# buffered-mult-pcb-a.net
KiCad netlist of a schematic drawn in EAGLE
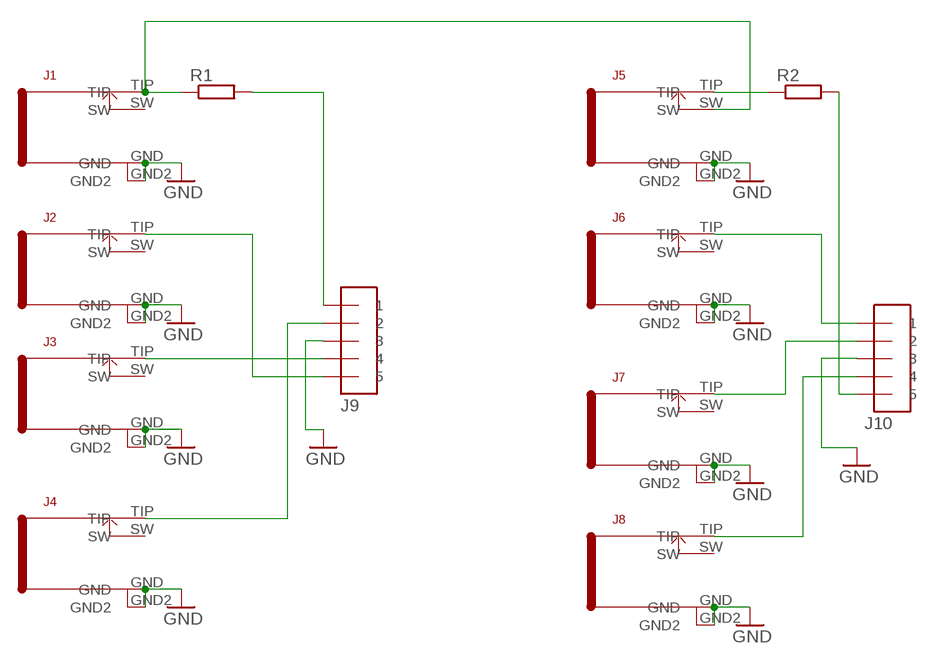
[diagram p0: schematic, sheet 1]

(export (version "E")
  (design (tool "Eeschema 10.0.6"))
  (components
    (comp (ref "J1")
      (value "WQP_PJ_301BM")
      (footprint "eagle-import:WQP_PJ_301BM")
      (libsource (lib "eagle-import") (part "WQP_PJ_301BM"))
    )
    (comp (ref "J2")
      (value "WQP_PJ_301BM")
      (footprint "eagle-import:WQP_PJ_301BM")
      (libsource (lib "eagle-import") (part "WQP_PJ_301BM"))
    )
    (comp (ref "J3")
      (value "WQP_PJ_301BM")
      (footprint "eagle-import:WQP_PJ_301BM")
      (libsource (lib "eagle-import") (part "WQP_PJ_301BM"))
    )
    (comp (ref "J4")
      (value "WQP_PJ_301BM")
      (footprint "eagle-import:WQP_PJ_301BM")
      (libsource (lib "eagle-import") (part "WQP_PJ_301BM"))
    )
    (comp (ref "J5")
      (value "WQP_PJ_301BM")
      (footprint "eagle-import:WQP_PJ_301BM")
      (libsource (lib "eagle-import") (part "WQP_PJ_301BM"))
    )
    (comp (ref "J6")
      (value "WQP_PJ_301BM")
      (footprint "eagle-import:WQP_PJ_301BM")
      (libsource (lib "eagle-import") (part "WQP_PJ_301BM"))
    )
    (comp (ref "J7")
      (value "WQP_PJ_301BM")
      (footprint "eagle-import:WQP_PJ_301BM")
      (libsource (lib "eagle-import") (part "WQP_PJ_301BM"))
    )
    (comp (ref "J8")
      (value "WQP_PJ_301BM")
      (footprint "eagle-import:WQP_PJ_301BM")
      (libsource (lib "eagle-import") (part "WQP_PJ_301BM"))
    )
    (comp (ref "J9")
      (value "5X1_2_54_HEADER")
      (footprint "eagle-import:5X1_2_54_HEADER")
      (libsource (lib "eagle-import") (part "5X1_2_54_HEADER"))
    )
    (comp (ref "J10")
      (value "5X1_2_54_HEADER")
      (footprint "eagle-import:5X1_2_54_HEADER")
      (libsource (lib "eagle-import") (part "5X1_2_54_HEADER"))
    )
    (comp (ref "R1")
      (value "R-EU_R0603")
      (footprint "eagle-import:R0603")
      (libsource (lib "eagle-import") (part "R-EU_R0603"))
    )
    (comp (ref "R2")
      (value "R-EU_R0603")
      (footprint "eagle-import:R0603")
      (libsource (lib "eagle-import") (part "R-EU_R0603"))
    )
  )
  (nets
    (net (code "1") (name "GND") (class "Default")
      (node (ref "J1") (pin "GND") (pinfunction "GND_GND") (pintype "passive"))
      (node (ref "J1") (pin "GND2") (pinfunction "GND2_GND2") (pintype "passive"))
      (node (ref "J10") (pin "3") (pinfunction "3_3") (pintype "bidirectional"))
      (node (ref "J2") (pin "GND") (pinfunction "GND_GND") (pintype "passive"))
      (node (ref "J2") (pin "GND2") (pinfunction "GND2_GND2") (pintype "passive"))
      (node (ref "J3") (pin "GND") (pinfunction "GND_GND") (pintype "passive"))
      (node (ref "J3") (pin "GND2") (pinfunction "GND2_GND2") (pintype "passive"))
      (node (ref "J4") (pin "GND") (pinfunction "GND_GND") (pintype "passive"))
      (node (ref "J4") (pin "GND2") (pinfunction "GND2_GND2") (pintype "passive"))
      (node (ref "J5") (pin "GND") (pinfunction "GND_GND") (pintype "passive"))
      (node (ref "J5") (pin "GND2") (pinfunction "GND2_GND2") (pintype "passive"))
      (node (ref "J6") (pin "GND") (pinfunction "GND_GND") (pintype "passive"))
      (node (ref "J6") (pin "GND2") (pinfunction "GND2_GND2") (pintype "passive"))
      (node (ref "J7") (pin "GND") (pinfunction "GND_GND") (pintype "passive"))
      (node (ref "J7") (pin "GND2") (pinfunction "GND2_GND2") (pintype "passive"))
      (node (ref "J8") (pin "GND") (pinfunction "GND_GND") (pintype "passive"))
      (node (ref "J8") (pin "GND2") (pinfunction "GND2_GND2") (pintype "passive"))
      (node (ref "J9") (pin "3") (pinfunction "3_3") (pintype "bidirectional"))
    )
    (net (code "2") (name "Net-(J1-PadTIP)") (class "Default")
      (node (ref "J1") (pin "TIP") (pinfunction "TIP_TIP") (pintype "passive"))
      (node (ref "J5") (pin "SW") (pinfunction "SW_SW") (pintype "passive"))
      (node (ref "R1") (pin "1") (pinfunction "1_1") (pintype "passive"))
    )
    (net (code "3") (name "Net-(J2-PadTIP)") (class "Default")
      (node (ref "J2") (pin "TIP") (pinfunction "TIP_TIP") (pintype "passive"))
      (node (ref "J9") (pin "5") (pinfunction "5_5") (pintype "bidirectional"))
    )
    (net (code "4") (name "Net-(J3-PadTIP)") (class "Default")
      (node (ref "J3") (pin "TIP") (pinfunction "TIP_TIP") (pintype "passive"))
      (node (ref "J9") (pin "4") (pinfunction "4_4") (pintype "bidirectional"))
    )
    (net (code "5") (name "Net-(J4-PadTIP)") (class "Default")
      (node (ref "J4") (pin "TIP") (pinfunction "TIP_TIP") (pintype "passive"))
      (node (ref "J9") (pin "2") (pinfunction "2_2") (pintype "bidirectional"))
    )
    (net (code "6") (name "Net-(J5-PadTIP)") (class "Default")
      (node (ref "J5") (pin "TIP") (pinfunction "TIP_TIP") (pintype "passive"))
      (node (ref "R2") (pin "1") (pinfunction "1_1") (pintype "passive"))
    )
    (net (code "7") (name "Net-(J9-Pad1)") (class "Default")
      (node (ref "J9") (pin "1") (pinfunction "1_1") (pintype "bidirectional"))
      (node (ref "R1") (pin "2") (pinfunction "2_2") (pintype "passive"))
    )
    (net (code "8") (name "Net-(J10-Pad1)") (class "Default")
      (node (ref "J10") (pin "1") (pinfunction "1_1") (pintype "bidirectional"))
      (node (ref "J6") (pin "TIP") (pinfunction "TIP_TIP") (pintype "passive"))
    )
    (net (code "9") (name "Net-(J10-Pad2)") (class "Default")
      (node (ref "J10") (pin "2") (pinfunction "2_2") (pintype "bidirectional"))
      (node (ref "J7") (pin "TIP") (pinfunction "TIP_TIP") (pintype "passive"))
    )
    (net (code "10") (name "Net-(J10-Pad4)") (class "Default")
      (node (ref "J10") (pin "4") (pinfunction "4_4") (pintype "bidirectional"))
      (node (ref "J8") (pin "TIP") (pinfunction "TIP_TIP") (pintype "passive"))
    )
    (net (code "11") (name "Net-(J10-Pad5)") (class "Default")
      (node (ref "J10") (pin "5") (pinfunction "5_5") (pintype "bidirectional"))
      (node (ref "R2") (pin "2") (pinfunction "2_2") (pintype "passive"))
    )
    (net (code "12") (name "unconnected-(J1-PadSW)") (class "Default")
      (node (ref "J1") (pin "SW") (pinfunction "SW_SW") (pintype "passive"))
    )
    (net (code "13") (name "unconnected-(J2-PadSW)") (class "Default")
      (node (ref "J2") (pin "SW") (pinfunction "SW_SW") (pintype "passive"))
    )
    (net (code "14") (name "unconnected-(J3-PadSW)") (class "Default")
      (node (ref "J3") (pin "SW") (pinfunction "SW_SW") (pintype "passive"))
    )
    (net (code "15") (name "unconnected-(J4-PadSW)") (class "Default")
      (node (ref "J4") (pin "SW") (pinfunction "SW_SW") (pintype "passive"))
    )
    (net (code "16") (name "unconnected-(J6-PadSW)") (class "Default")
      (node (ref "J6") (pin "SW") (pinfunction "SW_SW") (pintype "passive"))
    )
    (net (code "17") (name "unconnected-(J7-PadSW)") (class "Default")
      (node (ref "J7") (pin "SW") (pinfunction "SW_SW") (pintype "passive"))
    )
    (net (code "18") (name "unconnected-(J8-PadSW)") (class "Default")
      (node (ref "J8") (pin "SW") (pinfunction "SW_SW") (pintype "passive"))
    )
  )
)
